# ProPrj_usb__2025-12-14-12-49-50.net
KiCad netlist of a schematic drawn in EasyEDA Pro
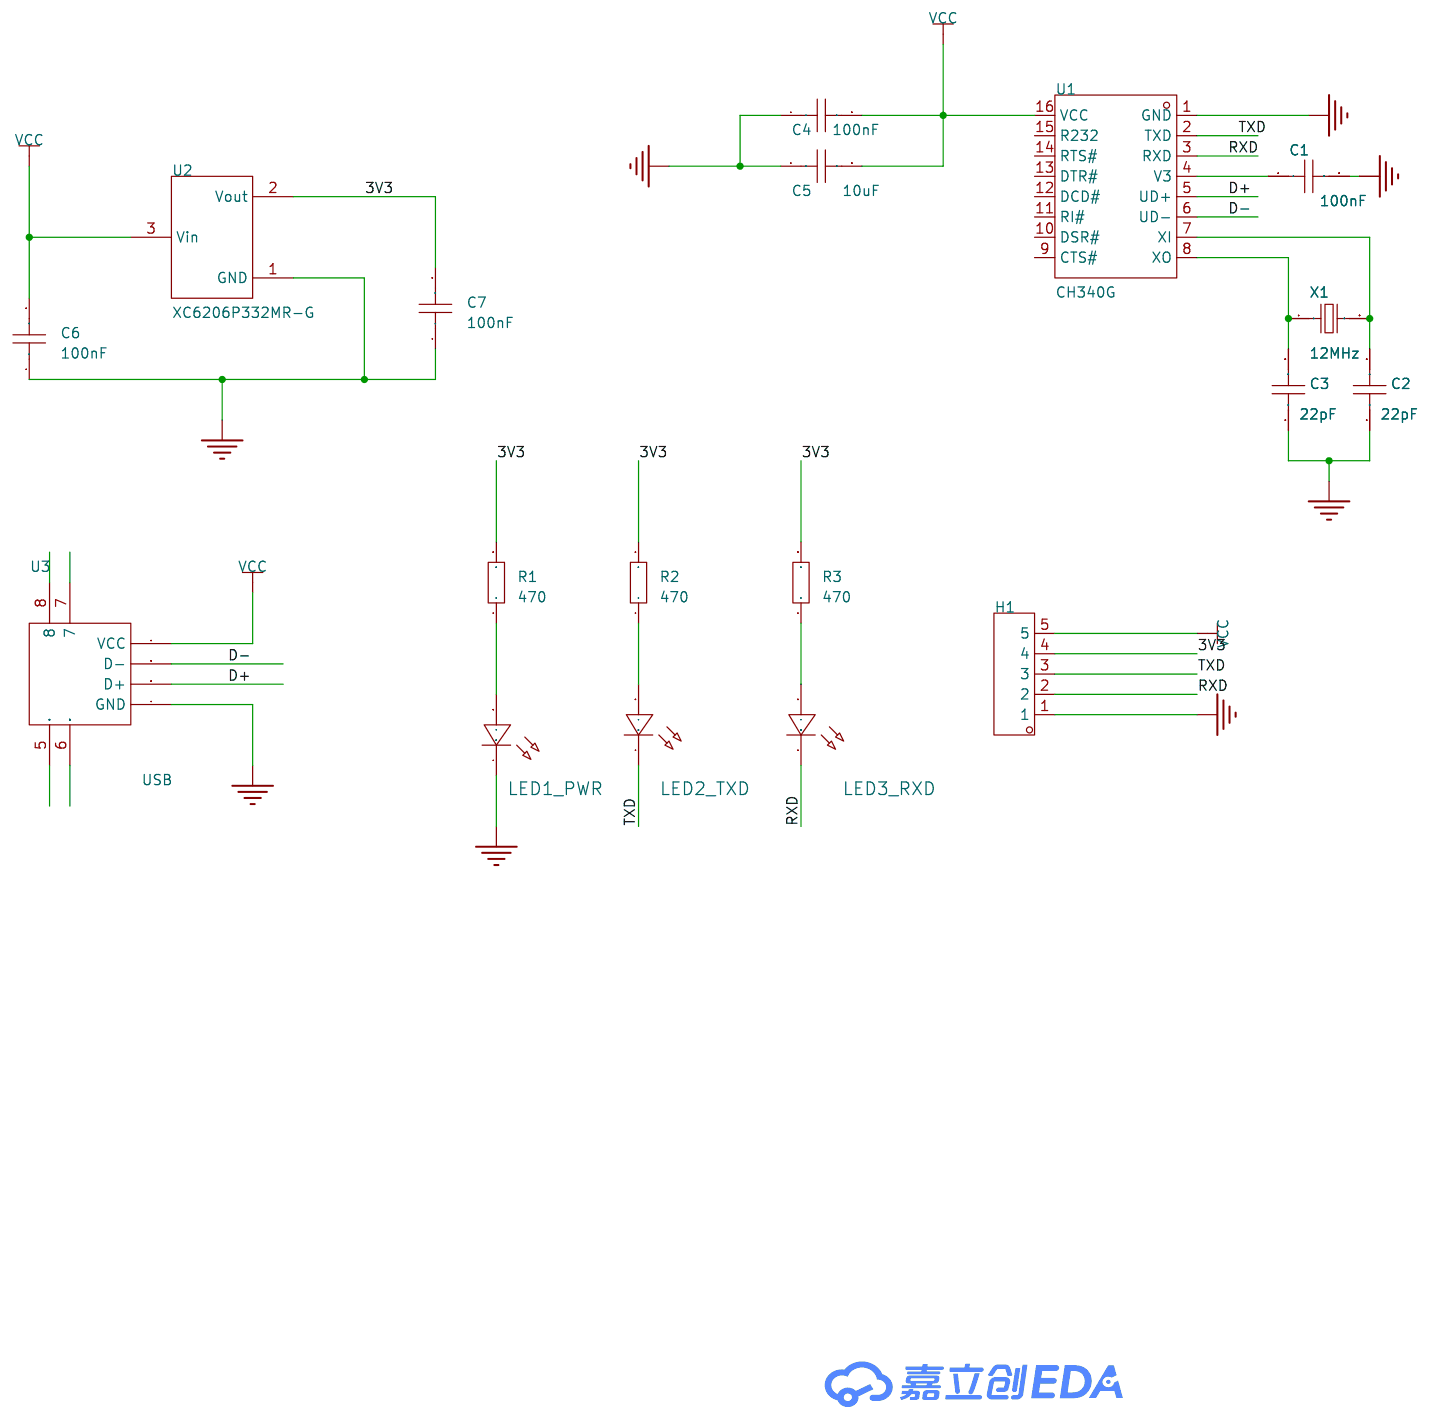
[diagram p0: schematic sheet]

(export (version "E")
  (design (tool "Eeschema 10.0.6"))
  (components
    (comp (ref "C1")
      (value "100nF")
      (footprint "easyedapro:C0603")
      (libsource (lib "easyedapro") (part "Capacitance"))
    )
    (comp (ref "C2")
      (value "22pF")
      (footprint "easyedapro:C0603")
      (libsource (lib "easyedapro") (part "Capacitance"))
    )
    (comp (ref "C3")
      (value "22pF")
      (footprint "easyedapro:C0603")
      (libsource (lib "easyedapro") (part "Capacitance"))
    )
    (comp (ref "C4")
      (value "100nF")
      (footprint "easyedapro:C0603")
      (libsource (lib "easyedapro") (part "Capacitance"))
    )
    (comp (ref "C5")
      (value "10uF")
      (footprint "easyedapro:C0603")
      (libsource (lib "easyedapro") (part "Capacitance"))
    )
    (comp (ref "C6")
      (value "100nF")
      (footprint "easyedapro:C0603")
      (libsource (lib "easyedapro") (part "Capacitance"))
    )
    (comp (ref "C7")
      (value "100nF")
      (footprint "easyedapro:C0603")
      (libsource (lib "easyedapro") (part "Capacitance"))
    )
    (comp (ref "H1")
      (value "~")
      (footprint "easyedapro:HDR-TH_5P-P2.54-V-M")
      (libsource (lib "easyedapro") (part "MTP125-1105S1"))
    )
    (comp (ref "LED1_PWR")
      (value "~")
      (footprint "easyedapro:LED_0603")
      (libsource (lib "easyedapro") (part "LED_R"))
    )
    (comp (ref "LED2_TXD")
      (value "~")
      (footprint "easyedapro:LED_0603")
      (libsource (lib "easyedapro") (part "LED_R"))
    )
    (comp (ref "LED3_RXD")
      (value "~")
      (footprint "easyedapro:LED_0603")
      (libsource (lib "easyedapro") (part "LED_R"))
    )
    (comp (ref "R1") (value "470") (footprint "easyedapro:R0603") (libsource (lib "easyedapro") (part "电阻")))
    (comp (ref "R2") (value "470") (footprint "easyedapro:R0603") (libsource (lib "easyedapro") (part "电阻")))
    (comp (ref "R3") (value "470") (footprint "easyedapro:R0603") (libsource (lib "easyedapro") (part "电阻")))
    (comp (ref "U1")
      (value "CH340G")
      (footprint "easyedapro:SOIC-16_L9.9-W3.9-P1.27-LS6.0-BL")
      (description "应用功能:USB转UART;接口协议:USB 2.0;数据速率:2Mbps;")
      (fields (field (name "Manufacturer") "WCH(南京沁恒)"))
      (libsource (lib "easyedapro") (part "CH340G"))
    )
    (comp (ref "U2")
      (value "XC6206P332MR-G")
      (footprint "easyedapro:SOT-23-3_L2.9-W1.6-P1.90-LS2.8-BR")
      (description "输出类型:固定;工作电压:6V;输出电压:3.3V;输出电流:200mA;电源纹波抑制比(PSRR):-;输出极性:正极;")
      (fields (field (name "Manufacturer") "TOREX(特瑞仕)"))
      (libsource (lib "easyedapro") (part "XC6206P332MR"))
    )
    (comp (ref "U3")
      (value "USB")
      (footprint "easyedapro:USB-SMD_USB_1")
      (libsource (lib "easyedapro") (part "USB"))
    )
    (comp (ref "X1")
      (value "12MHz")
      (footprint "easyedapro:CRYSTAL-SMD_L5.0-W3.2")
      (description "晶振类型:贴片晶振;频率:12MHz;常温频差:±20ppm;负载电容:20pF;频率稳定度:±30ppm;")
      (fields
        (field (name "Manufacturer Part") "XC53G2-12.000-F20LJDT")
        (field (name "Manufacturer") "HCI(杭晶)")
      )
      (libsource (lib "easyedapro") (part "XC53G2-12.000-F20LJDT"))
    )
  )
  (nets
    (net (code "1") (name "/3V3") (class "Default")
      (node (ref "C7") (pin "2") (pinfunction "2_2") (pintype "input"))
      (node (ref "H1") (pin "4") (pinfunction "4_4") (pintype "unspecified"))
      (node (ref "R1") (pin "2") (pinfunction "2_2") (pintype "input"))
      (node (ref "R2") (pin "2") (pinfunction "2_2") (pintype "input"))
      (node (ref "R3") (pin "2") (pinfunction "2_2") (pintype "input"))
      (node (ref "U2") (pin "2") (pinfunction "Vout_2") (pintype "unspecified"))
    )
    (net (code "2") (name "/D+") (class "Default")
      (node (ref "U1") (pin "5") (pinfunction "UD+_5") (pintype "unspecified"))
      (node (ref "U3") (pin "3") (pinfunction "D+_3") (pintype "input"))
    )
    (net (code "3") (name "/D-") (class "Default")
      (node (ref "U1") (pin "6") (pinfunction "UD-_6") (pintype "unspecified"))
      (node (ref "U3") (pin "2") (pinfunction "D-_2") (pintype "input"))
    )
    (net (code "4") (name "/RXD") (class "Default")
      (node (ref "H1") (pin "2") (pinfunction "2_2") (pintype "unspecified"))
      (node (ref "LED3_RXD") (pin "1") (pinfunction "C_1") (pintype "input"))
      (node (ref "U1") (pin "3") (pinfunction "RXD_3") (pintype "unspecified"))
    )
    (net (code "5") (name "/TXD") (class "Default")
      (node (ref "H1") (pin "3") (pinfunction "3_3") (pintype "unspecified"))
      (node (ref "LED2_TXD") (pin "1") (pinfunction "C_1") (pintype "input"))
      (node (ref "U1") (pin "2") (pinfunction "TXD_2") (pintype "unspecified"))
    )
    (net (code "6") (name "GND") (class "Default")
      (node (ref "C1") (pin "2") (pinfunction "2_2") (pintype "input"))
      (node (ref "C2") (pin "1") (pinfunction "1_1") (pintype "input"))
      (node (ref "C3") (pin "1") (pinfunction "1_1") (pintype "input"))
      (node (ref "C4") (pin "1") (pinfunction "1_1") (pintype "input"))
      (node (ref "C5") (pin "1") (pinfunction "1_1") (pintype "input"))
      (node (ref "C6") (pin "1") (pinfunction "1_1") (pintype "input"))
      (node (ref "C7") (pin "1") (pinfunction "1_1") (pintype "input"))
      (node (ref "H1") (pin "1") (pinfunction "1_1") (pintype "unspecified"))
      (node (ref "LED1_PWR") (pin "1") (pinfunction "C_1") (pintype "input"))
      (node (ref "U1") (pin "1") (pinfunction "GND_1") (pintype "unspecified"))
      (node (ref "U2") (pin "1") (pinfunction "GND_1") (pintype "unspecified"))
      (node (ref "U3") (pin "4") (pinfunction "GND_4") (pintype "input"))
    )
    (net (code "7") (name "Net-(LED1_PWR-A)") (class "Default")
      (node (ref "LED1_PWR") (pin "2") (pinfunction "A_2") (pintype "input"))
      (node (ref "R1") (pin "1") (pinfunction "1_1") (pintype "input"))
    )
    (net (code "8") (name "Net-(LED2_TXD-A)") (class "Default")
      (node (ref "LED2_TXD") (pin "2") (pinfunction "A_2") (pintype "input"))
      (node (ref "R2") (pin "1") (pinfunction "1_1") (pintype "input"))
    )
    (net (code "9") (name "Net-(LED3_RXD-A)") (class "Default")
      (node (ref "LED3_RXD") (pin "2") (pinfunction "A_2") (pintype "input"))
      (node (ref "R3") (pin "1") (pinfunction "1_1") (pintype "input"))
    )
    (net (code "10") (name "Net-(U1-V3)") (class "Default")
      (node (ref "C1") (pin "1") (pinfunction "1_1") (pintype "input"))
      (node (ref "U1") (pin "4") (pinfunction "V3_4") (pintype "unspecified"))
    )
    (net (code "11") (name "Net-(U1-XI)") (class "Default")
      (node (ref "C2") (pin "2") (pinfunction "2_2") (pintype "input"))
      (node (ref "U1") (pin "7") (pinfunction "XI_7") (pintype "unspecified"))
      (node (ref "X1") (pin "2") (pinfunction "2_2") (pintype "unspecified"))
    )
    (net (code "12") (name "Net-(U1-XO)") (class "Default")
      (node (ref "C3") (pin "2") (pinfunction "2_2") (pintype "input"))
      (node (ref "U1") (pin "8") (pinfunction "XO_8") (pintype "unspecified"))
      (node (ref "X1") (pin "1") (pinfunction "1_1") (pintype "unspecified"))
    )
    (net (code "13") (name "VCC") (class "Default")
      (node (ref "C4") (pin "2") (pinfunction "2_2") (pintype "input"))
      (node (ref "C5") (pin "2") (pinfunction "2_2") (pintype "input"))
      (node (ref "C6") (pin "2") (pinfunction "2_2") (pintype "input"))
      (node (ref "H1") (pin "5") (pinfunction "5_5") (pintype "unspecified"))
      (node (ref "U1") (pin "16") (pinfunction "VCC_16") (pintype "unspecified"))
      (node (ref "U2") (pin "3") (pinfunction "Vin_3") (pintype "unspecified"))
      (node (ref "U3") (pin "1") (pinfunction "VCC_1") (pintype "input"))
    )
    (net (code "14") (name "unconnected-(U1-CTS#-Pad9)") (class "Default")
      (node (ref "U1") (pin "9") (pinfunction "CTS#_9") (pintype "unspecified"))
    )
    (net (code "15") (name "unconnected-(U1-DCD#-Pad12)") (class "Default")
      (node (ref "U1") (pin "12") (pinfunction "DCD#_12") (pintype "unspecified"))
    )
    (net (code "16") (name "unconnected-(U1-DSR#-Pad10)") (class "Default")
      (node (ref "U1") (pin "10") (pinfunction "DSR#_10") (pintype "unspecified"))
    )
    (net (code "17") (name "unconnected-(U1-DTR#-Pad13)") (class "Default")
      (node (ref "U1") (pin "13") (pinfunction "DTR#_13") (pintype "unspecified"))
    )
    (net (code "18") (name "unconnected-(U1-R232-Pad15)") (class "Default")
      (node (ref "U1") (pin "15") (pinfunction "R232_15") (pintype "unspecified"))
    )
    (net (code "19") (name "unconnected-(U1-RI#-Pad11)") (class "Default")
      (node (ref "U1") (pin "11") (pinfunction "RI#_11") (pintype "unspecified"))
    )
    (net (code "20") (name "unconnected-(U1-RTS#-Pad14)") (class "Default")
      (node (ref "U1") (pin "14") (pinfunction "RTS#_14") (pintype "unspecified"))
    )
    (net (code "21") (name "unconnected-(U3-Pad7)") (class "Default")
      (node (ref "U3") (pin "7") (pinfunction "7_7") (pintype "unspecified"))
    )
    (net (code "22") (name "unconnected-(U3-Pad8)") (class "Default")
      (node (ref "U3") (pin "8") (pinfunction "8_8") (pintype "unspecified"))
    )
    (net (code "23") (name "unconnected-(U3-SH1-Pad5)") (class "Default")
      (node (ref "U3") (pin "5") (pinfunction "SH1_5") (pintype "unspecified"))
    )
    (net (code "24") (name "unconnected-(U3-SH2-Pad6)") (class "Default")
      (node (ref "U3") (pin "6") (pinfunction "SH2_6") (pintype "unspecified"))
    )
  )
)
